# 10_SENSORS_CAN_485.net
KiCad netlist of a schematic drawn in Altium Designer
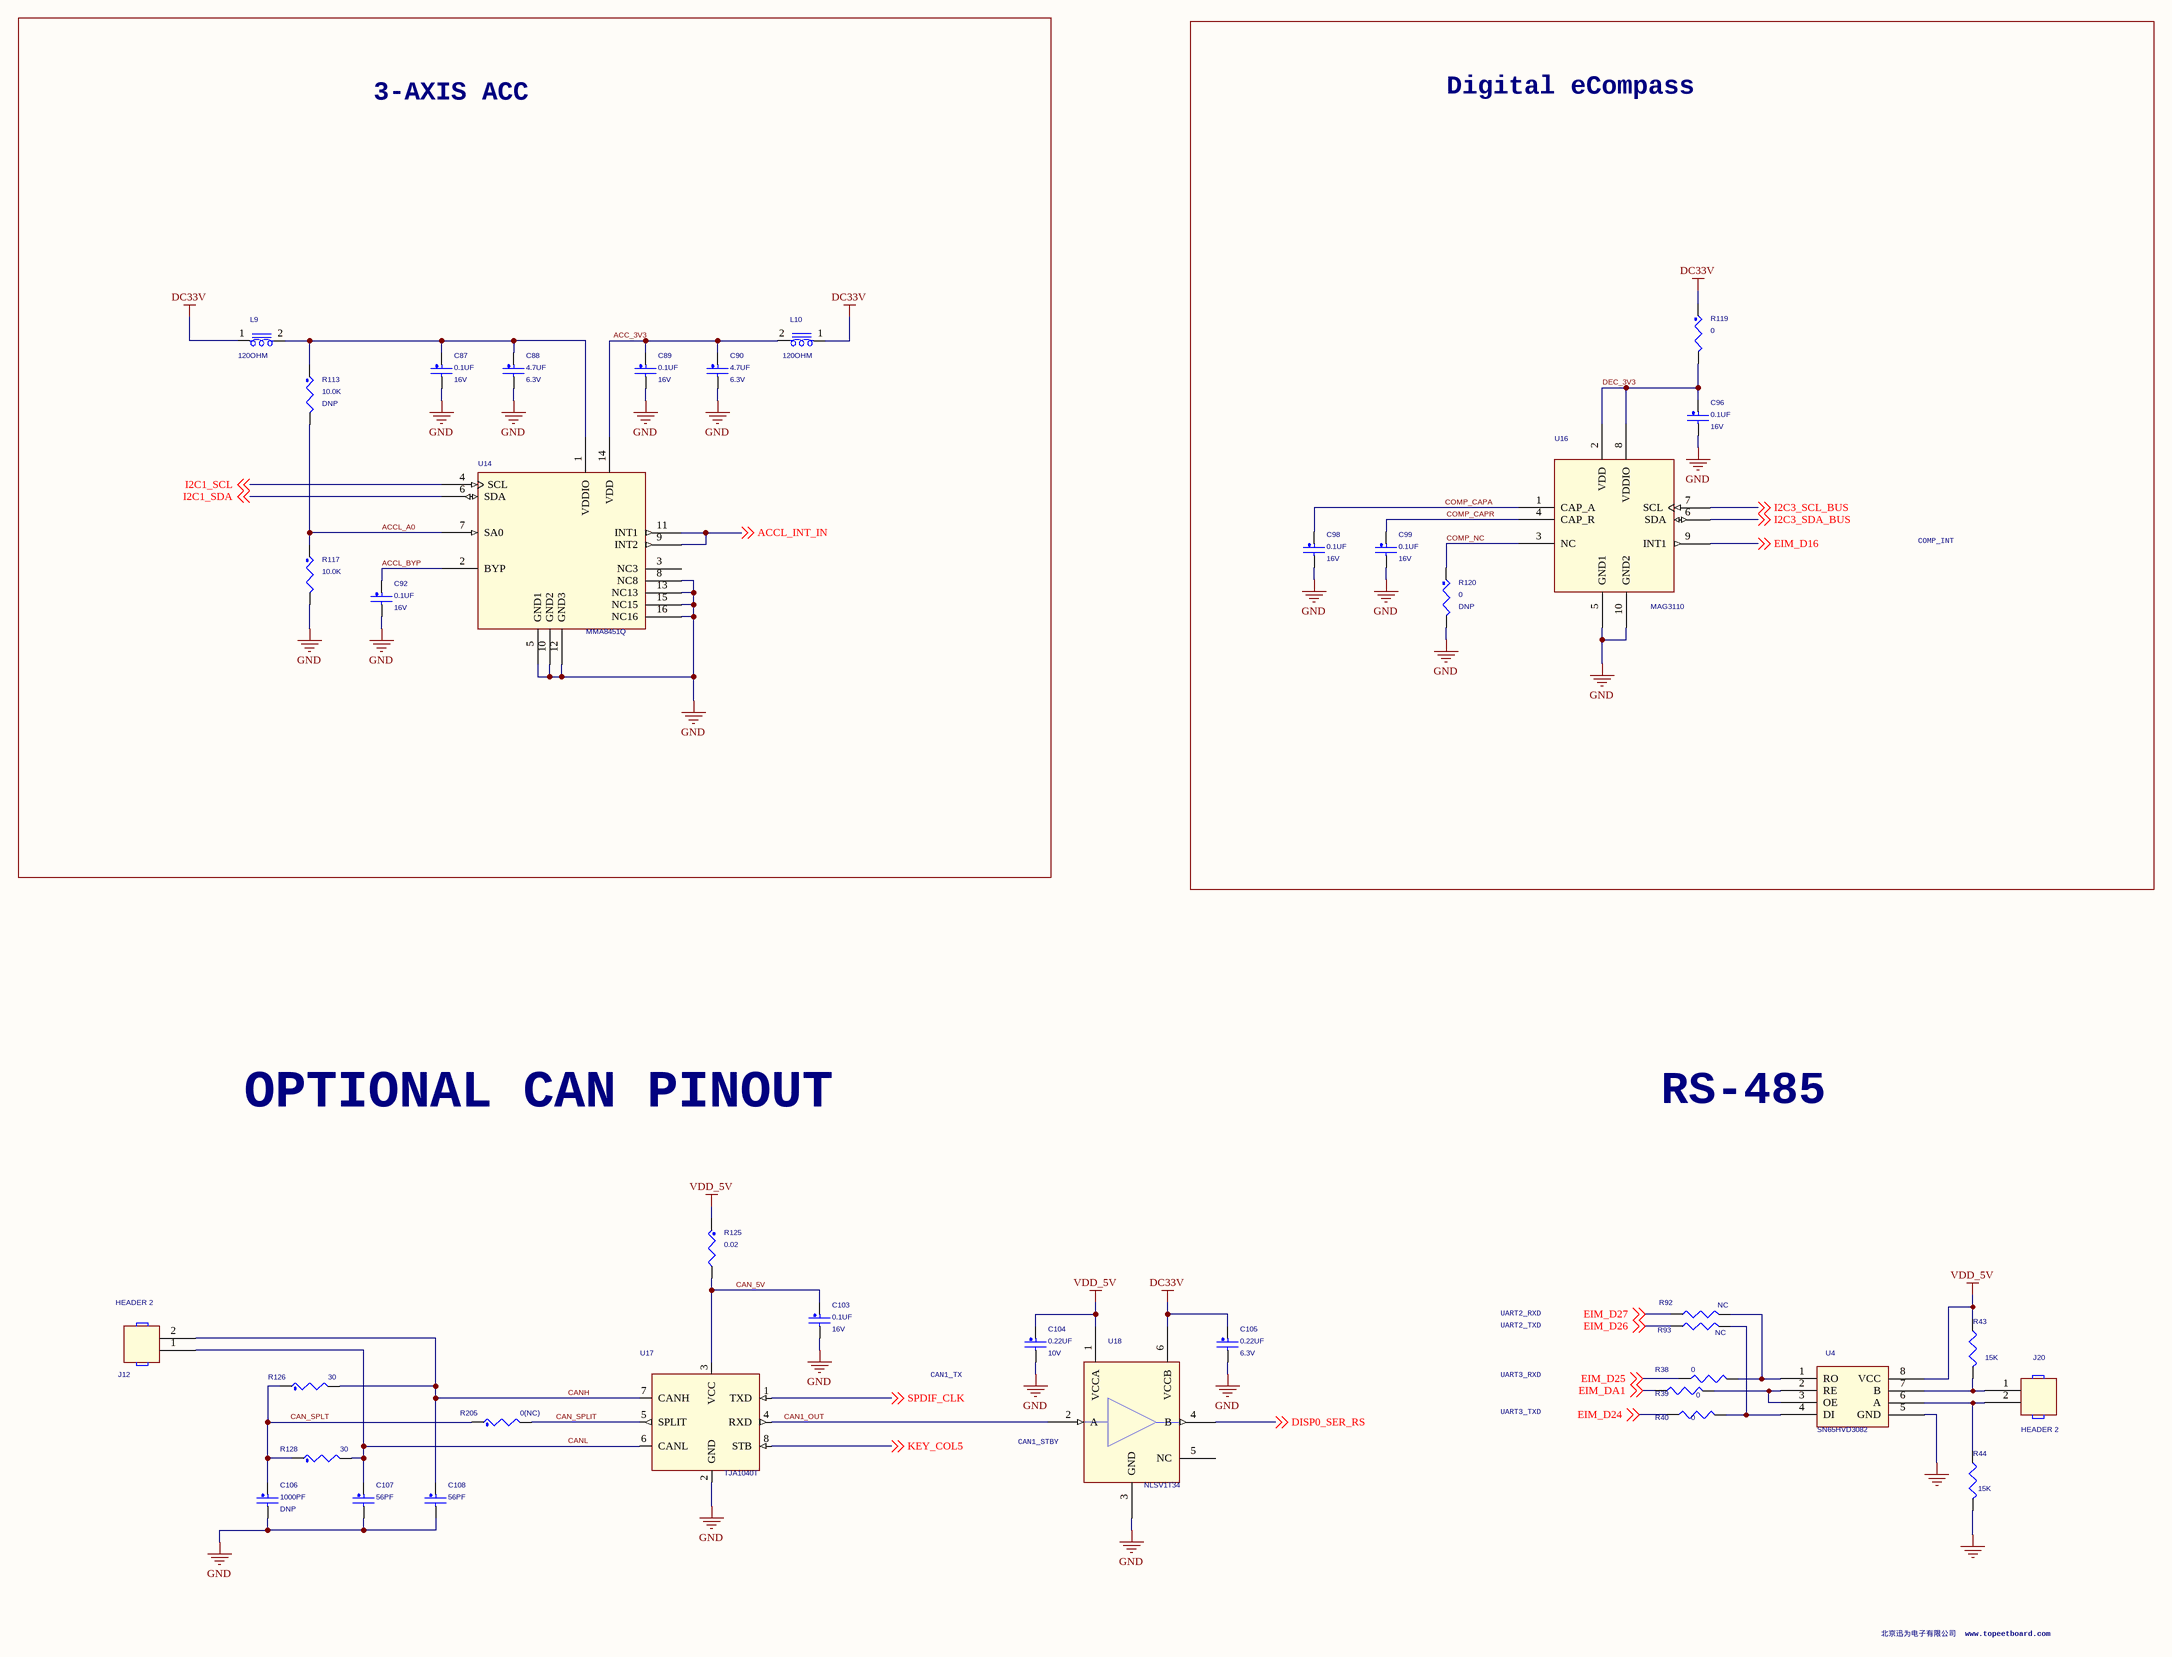
[diagram p0: 10 SENSORS,CAN,485.SchDoc]

(export (version "E")
  (design (tool "Eeschema 10.0.6"))
  (components
    (comp (ref "C87")
      (value "0.1UF")
      (description "CAP CER 0.1UF 16V 10% X7R 0402")
      (fields (field (name "TOLERANCE") "10%") (field (name "WVDC") "16V") (field (name "VOLTAGE") "16V"))
      (libsource (lib "*") (part "CAP_NP"))
    )
    (comp (ref "C88")
      (value "4.7UF")
      (description "CAP CER 4.7UF 6.3V 10% X5R 0603")
      (fields (field (name "TOLERANCE") "10%") (field (name "WVDC") "6.3V") (field (name "VOLTAGE") "6.3V"))
      (libsource (lib "*") (part "CAP_NP"))
    )
    (comp (ref "C89")
      (value "0.1UF")
      (description "CAP CER 0.1UF 16V 10% X7R 0402")
      (fields (field (name "TOLERANCE") "10%") (field (name "WVDC") "16V") (field (name "VOLTAGE") "16V"))
      (libsource (lib "*") (part "CAP_NP"))
    )
    (comp (ref "C90")
      (value "4.7UF")
      (description "CAP CER 4.7UF 6.3V 10% X5R 0603")
      (fields (field (name "VOLTAGE") "6.3V") (field (name "WVDC") "6.3V") (field (name "TOLERANCE") "10%"))
      (libsource (lib "*") (part "CAP_NP"))
    )
    (comp (ref "C92")
      (value "0.1UF")
      (description "CAP CER 0.1UF 16V 10% X7R 0402")
      (fields (field (name "VOLTAGE") "16V") (field (name "WVDC") "16V") (field (name "TOLERANCE") "10%"))
      (libsource (lib "*") (part "CAP_NP"))
    )
    (comp (ref "C96")
      (value "0.1UF")
      (description "CAP CER 0.1UF 16V 10% X7R 0402")
      (fields (field (name "TOLERANCE") "10%") (field (name "WVDC") "16V") (field (name "VOLTAGE") "16V"))
      (libsource (lib "*") (part "CAP_NP"))
    )
    (comp (ref "C98")
      (value "0.1UF")
      (description "CAP CER 0.1UF 16V 10% X7R 0402")
      (fields (field (name "TOLERANCE") "10%") (field (name "WVDC") "16V") (field (name "VOLTAGE") "16V"))
      (libsource (lib "*") (part "CAP_NP"))
    )
    (comp (ref "C99")
      (value "0.1UF")
      (description "CAP CER 0.1UF 16V 10% X7R 0402")
      (fields (field (name "TOLERANCE") "10%") (field (name "WVDC") "16V") (field (name "VOLTAGE") "16V"))
      (libsource (lib "*") (part "CAP_NP"))
    )
    (comp (ref "C103")
      (value "0.1UF")
      (description "CAP CER 0.1UF 16V 10% X7R 0402")
      (fields (field (name "VOLTAGE") "16V") (field (name "TOLERANCE") "10%") (field (name "WVDC") "16V"))
      (libsource (lib "*") (part "CAP_NP"))
    )
    (comp (ref "C104")
      (value "0.22UF")
      (description "CAP CER 0.22UF 10V 20% X5R 0201")
      (fields (field (name "VOLTAGE") "10V") (field (name "TOLERANCE") "20%") (field (name "WVDC") "10V"))
      (libsource (lib "*") (part "CAP_NP"))
    )
    (comp (ref "C105")
      (value "0.22UF")
      (description "CAP CER 0.22UF 6.3V 20% X5R 0201")
      (fields (field (name "VOLTAGE") "6.3V") (field (name "WVDC") "6.3V") (field (name "TOLERANCE") "20%"))
      (libsource (lib "*") (part "CAP_NP"))
    )
    (comp (ref "C106")
      (value "1000PF")
      (description "CAP CER 1000PF 50V 5% C0G 0402")
      (fields (field (name "ASSY_OPT") "DNP"))
      (libsource (lib "*") (part "CAP_NP"))
    )
    (comp (ref "C107")
      (value "56PF")
      (description "CAP CER 56PF 25V 5% C0G CC0201")
      (fields (field (name "VOLTAGE") "25V") (field (name "TOLERANCE") "5%"))
      (libsource (lib "*") (part "CAP_NP"))
    )
    (comp (ref "C108")
      (value "56PF")
      (description "CAP CER 56PF 25V 5% C0G CC0201")
      (fields (field (name "VOLTAGE") "25V") (field (name "TOLERANCE") "5%"))
      (libsource (lib "*") (part "CAP_NP"))
    )
    (comp (ref "J12") (value "HEADER 2") (libsource (lib "*") (part "HEADER 2")))
    (comp (ref "J20") (value "HEADER 2") (libsource (lib "") (part "HEADER 2_1")))
    (comp (ref "L9")
      (value "120OHM")
      (description "IND FER BEAD 120OHM@100MHZ 2A 25% 0603")
      (fields (field (name "TOLERANCE") "25%"))
      (libsource (lib "") (part "BEAD_0_1"))
    )
    (comp (ref "L10")
      (value "120OHM")
      (description "IND FER BEAD 120OHM@100MHZ 2A 25% 0603")
      (fields (field (name "TOLERANCE") "25%"))
      (libsource (lib "*") (part "BEAD_0"))
    )
    (comp (ref "R38") (value "0") (footprint "R1005") (libsource (lib "*") (part "R1005_0_Dup1")))
    (comp (ref "R39") (value "0") (footprint "R1005") (libsource (lib "*") (part "R1005_0_Dup1")))
    (comp (ref "R40") (value "0") (footprint "R1005") (libsource (lib "*") (part "R1005_0_Dup1")))
    (comp (ref "R43") (value "15K") (footprint "R1005") (libsource (lib "*") (part "R1005_0_Dup1")))
    (comp (ref "R44") (value "15K") (footprint "R1005") (libsource (lib "*") (part "R1005_0_Dup1")))
    (comp (ref "R92") (value "NC") (footprint "R1005") (libsource (lib "*") (part "R1005_0_Dup1")))
    (comp (ref "R93") (value "NC") (footprint "R1005") (libsource (lib "*") (part "R1005_0_Dup1")))
    (comp (ref "R113")
      (value "10.0K")
      (description "RES MF 10.0K 1/16W 1% AEC-Q200 0402")
      (fields (field (name "ASSY_OPT") "DNP") (field (name "TOLERANCE") "1%"))
      (libsource (lib "*") (part "RES_Dup1"))
    )
    (comp (ref "R117")
      (value "10.0K")
      (description "RES MF 10.0K 1/16W 1% AEC-Q200 0402")
      (fields (field (name "TOLERANCE") "1%"))
      (libsource (lib "*") (part "RES_Dup1"))
    )
    (comp (ref "R119")
      (value "0")
      (description "RES MF ZERO OHM 1/10W -- 0402")
      (libsource (lib "*") (part "RES_Dup1"))
    )
    (comp (ref "R120")
      (value "0")
      (description "RES MF ZERO OHM 1/10W -- 0402")
      (fields (field (name "ASSY_OPT") "DNP"))
      (libsource (lib "*") (part "RES_Dup1"))
    )
    (comp (ref "R125")
      (value "0.02")
      (description "RES MF 0.02 OHM 1/8W 1% 0805")
      (libsource (lib "*") (part "RES_Dup1"))
    )
    (comp (ref "R126")
      (value "30")
      (description "RES MF 30 OHM 1/16W 1% 0402")
      (fields (field (name "TOLERANCE") "1%"))
      (libsource (lib "*") (part "RES_Dup1"))
    )
    (comp (ref "R128")
      (value "30")
      (description "RES MF 30 OHM 1/16W 1% 0402")
      (fields (field (name "TOLERANCE") "1%"))
      (libsource (lib "*") (part "RES_Dup1"))
    )
    (comp (ref "R205")
      (value "0(NC)")
      (description "RES MF 30 OHM 1/16W 1% 0402")
      (fields (field (name "TOLERANCE") "1%"))
      (libsource (lib "*") (part "RES_Dup1"))
    )
    (comp (ref "U4") (value "SN65HVD3082") (libsource (lib "*") (part "SN65HVD3082")))
    (comp (ref "U14")
      (value "MMA8451Q")
      (description "IC 3-AXIS DIG ACCELEROMETER 14/8BIT 1.95-3.6V QFN16")
      (libsource (lib "*") (part "MMA8451Q_16P_A"))
    )
    (comp (ref "U16")
      (value "MAG3110")
      (description "IC 3-AXIS DIGITAL MAGNETOMETER 1.95-3.6V DFN10")
      (libsource (lib "*") (part "MAG3112_DFN_10P"))
    )
    (comp (ref "U17")
      (value "TJA1040T")
      (description "IC XCVR CAN HS 5V SO8")
      (libsource (lib "*") (part "TJA1040T_SO_8P"))
    )
    (comp (ref "U18")
      (value "NLSV1T34")
      (description "IC VXLTR 1 BIT DUAL-SUPPLY 0.9-4.5V 613AF")
      (libsource (lib "*") (part "NLSV1T34"))
    )
  )
  (nets
    (net (code "1") (name "/ACCL_A0") (class "Default")
      (node (ref "R113") (pin "2") (pinfunction "2_2") (pintype "passive"))
      (node (ref "R117") (pin "1") (pinfunction "1_1") (pintype "passive"))
      (node (ref "U14") (pin "7") (pinfunction "SA0_7") (pintype "input"))
    )
    (net (code "2") (name "/ACCL_BYP") (class "Default")
      (node (ref "C92") (pin "1") (pinfunction "1_1") (pintype "passive"))
      (node (ref "U14") (pin "2") (pinfunction "BYP_2") (pintype "passive"))
    )
    (net (code "3") (name "/ACC_3V3") (class "Default")
      (node (ref "C89") (pin "1") (pinfunction "1_1") (pintype "passive"))
      (node (ref "C90") (pin "1") (pinfunction "1_1") (pintype "passive"))
      (node (ref "L10") (pin "2") (pinfunction "2_2") (pintype "passive"))
      (node (ref "U14") (pin "14") (pinfunction "VDD_14") (pintype "power_in"))
    )
    (net (code "4") (name "/CAN1_OUT") (class "Default")
      (node (ref "U17") (pin "4") (pinfunction "RXD_4") (pintype "output"))
      (node (ref "U18") (pin "2") (pinfunction "A_2") (pintype "input"))
    )
    (net (code "5") (name "/CANH") (class "Default")
      (node (ref "C108") (pin "1") (pinfunction "1_1") (pintype "passive"))
      (node (ref "J12") (pin "2") (pinfunction "2_2") (pintype "passive"))
      (node (ref "R126") (pin "2") (pinfunction "2_2") (pintype "passive"))
      (node (ref "U17") (pin "7") (pinfunction "CANH_7") (pintype "bidirectional"))
    )
    (net (code "6") (name "/CANL") (class "Default")
      (node (ref "C107") (pin "1") (pinfunction "1_1") (pintype "passive"))
      (node (ref "J12") (pin "1") (pinfunction "1_1") (pintype "passive"))
      (node (ref "R128") (pin "2") (pinfunction "2_2") (pintype "passive"))
      (node (ref "U17") (pin "6") (pinfunction "CANL_6") (pintype "bidirectional"))
    )
    (net (code "7") (name "/CAN_5V") (class "Default")
      (node (ref "C103") (pin "1") (pinfunction "1_1") (pintype "passive"))
      (node (ref "R125") (pin "2") (pinfunction "2_2") (pintype "passive"))
      (node (ref "U17") (pin "3") (pinfunction "VCC_3") (pintype "power_in"))
    )
    (net (code "8") (name "/CAN_SPLIT") (class "Default")
      (node (ref "R205") (pin "2") (pinfunction "2_2") (pintype "passive"))
      (node (ref "U17") (pin "5") (pinfunction "SPLIT_5") (pintype "output"))
    )
    (net (code "9") (name "/CAN_SPLT") (class "Default")
      (node (ref "C106") (pin "1") (pinfunction "1_1") (pintype "passive"))
      (node (ref "R126") (pin "1") (pinfunction "1_1") (pintype "passive"))
      (node (ref "R128") (pin "1") (pinfunction "1_1") (pintype "passive"))
      (node (ref "R205") (pin "1") (pinfunction "1_1") (pintype "passive"))
    )
    (net (code "10") (name "/COMP_CAPA") (class "Default")
      (node (ref "C98") (pin "1") (pinfunction "1_1") (pintype "passive"))
      (node (ref "U16") (pin "1") (pinfunction "CAP_A_1") (pintype "passive"))
    )
    (net (code "11") (name "/COMP_CAPR") (class "Default")
      (node (ref "C99") (pin "1") (pinfunction "1_1") (pintype "passive"))
      (node (ref "U16") (pin "4") (pinfunction "CAP_R_4") (pintype "passive"))
    )
    (net (code "12") (name "/COMP_NC") (class "Default")
      (node (ref "R120") (pin "1") (pinfunction "1_1") (pintype "passive"))
      (node (ref "U16") (pin "3") (pinfunction "NC_3") (pintype "passive"))
    )
    (net (code "13") (name "/DEC_3V3") (class "Default")
      (node (ref "C96") (pin "1") (pinfunction "1_1") (pintype "passive"))
      (node (ref "R119") (pin "2") (pinfunction "2_2") (pintype "passive"))
      (node (ref "U16") (pin "2") (pinfunction "VDD_2") (pintype "power_in"))
      (node (ref "U16") (pin "8") (pinfunction "VDDIO_8") (pintype "power_in"))
    )
    (net (code "14") (name "ACCL_INT_IN") (class "Default")
      (node (ref "U14") (pin "11") (pinfunction "INT1_11") (pintype "output"))
      (node (ref "U14") (pin "9") (pinfunction "INT2_9") (pintype "output"))
    )
    (net (code "15") (name "DC33V") (class "Default")
      (node (ref "C105") (pin "1") (pinfunction "1_1") (pintype "passive"))
      (node (ref "L10") (pin "1") (pinfunction "1_1") (pintype "passive"))
      (node (ref "L9") (pin "1") (pinfunction "1_1") (pintype "passive"))
      (node (ref "R119") (pin "1") (pinfunction "1_1") (pintype "passive"))
      (node (ref "U18") (pin "6") (pinfunction "VCCB_6") (pintype "power_in"))
    )
    (net (code "16") (name "DISP0_SER_RS") (class "Default")
      (node (ref "U18") (pin "4") (pinfunction "B_4") (pintype "output"))
    )
    (net (code "17") (name "EIM_D16") (class "Default")
      (node (ref "U16") (pin "9") (pinfunction "INT1_9") (pintype "output"))
    )
    (net (code "18") (name "EIM_D24") (class "Default")
      (node (ref "R40") (pin "2") (pinfunction "2_2") (pintype "passive"))
    )
    (net (code "19") (name "EIM_D25") (class "Default")
      (node (ref "R38") (pin "2") (pinfunction "2_2") (pintype "passive"))
    )
    (net (code "20") (name "EIM_D26") (class "Default")
      (node (ref "R93") (pin "1") (pinfunction "1_1") (pintype "passive"))
    )
    (net (code "21") (name "EIM_D27") (class "Default")
      (node (ref "R92") (pin "1") (pinfunction "1_1") (pintype "passive"))
    )
    (net (code "22") (name "EIM_DA1") (class "Default")
      (node (ref "R39") (pin "2") (pinfunction "2_2") (pintype "passive"))
    )
    (net (code "23") (name "GND") (class "Default")
      (node (ref "C103") (pin "2") (pinfunction "2_2") (pintype "passive"))
      (node (ref "C104") (pin "2") (pinfunction "2_2") (pintype "passive"))
      (node (ref "C105") (pin "2") (pinfunction "2_2") (pintype "passive"))
      (node (ref "C106") (pin "2") (pinfunction "2_2") (pintype "passive"))
      (node (ref "C107") (pin "2") (pinfunction "2_2") (pintype "passive"))
      (node (ref "C108") (pin "2") (pinfunction "2_2") (pintype "passive"))
      (node (ref "C87") (pin "2") (pinfunction "2_2") (pintype "passive"))
      (node (ref "C88") (pin "2") (pinfunction "2_2") (pintype "passive"))
      (node (ref "C89") (pin "2") (pinfunction "2_2") (pintype "passive"))
      (node (ref "C90") (pin "2") (pinfunction "2_2") (pintype "passive"))
      (node (ref "C92") (pin "2") (pinfunction "2_2") (pintype "passive"))
      (node (ref "C96") (pin "2") (pinfunction "2_2") (pintype "passive"))
      (node (ref "C98") (pin "2") (pinfunction "2_2") (pintype "passive"))
      (node (ref "C99") (pin "2") (pinfunction "2_2") (pintype "passive"))
      (node (ref "R117") (pin "2") (pinfunction "2_2") (pintype "passive"))
      (node (ref "R120") (pin "2") (pinfunction "2_2") (pintype "passive"))
      (node (ref "R44") (pin "1") (pinfunction "1_1") (pintype "passive"))
      (node (ref "U14") (pin "10") (pinfunction "GND2_10") (pintype "power_in"))
      (node (ref "U14") (pin "12") (pinfunction "GND3_12") (pintype "power_in"))
      (node (ref "U14") (pin "13") (pinfunction "NC13_13") (pintype "passive"))
      (node (ref "U14") (pin "15") (pinfunction "NC15_15") (pintype "passive"))
      (node (ref "U14") (pin "16") (pinfunction "NC16_16") (pintype "passive"))
      (node (ref "U14") (pin "5") (pinfunction "GND1_5") (pintype "power_in"))
      (node (ref "U14") (pin "8") (pinfunction "NC8_8") (pintype "passive"))
      (node (ref "U16") (pin "10") (pinfunction "GND2_10") (pintype "power_in"))
      (node (ref "U16") (pin "5") (pinfunction "GND1_5") (pintype "power_in"))
      (node (ref "U17") (pin "2") (pinfunction "GND_2") (pintype "power_in"))
      (node (ref "U18") (pin "3") (pinfunction "GND_3") (pintype "power_in"))
      (node (ref "U4") (pin "5") (pinfunction "GND_5") (pintype "passive"))
    )
    (net (code "24") (name "I2C1_SCL") (class "Default")
      (node (ref "U14") (pin "4") (pinfunction "SCL_4") (pintype "input"))
    )
    (net (code "25") (name "I2C1_SDA") (class "Default")
      (node (ref "U14") (pin "6") (pinfunction "SDA_6") (pintype "bidirectional"))
    )
    (net (code "26") (name "I2C3_SCL_BUS") (class "Default")
      (node (ref "U16") (pin "7") (pinfunction "SCL_7") (pintype "input"))
    )
    (net (code "27") (name "I2C3_SDA_BUS") (class "Default")
      (node (ref "U16") (pin "6") (pinfunction "SDA_6") (pintype "bidirectional"))
    )
    (net (code "28") (name "KEY_COL5") (class "Default")
      (node (ref "U17") (pin "8") (pinfunction "STB_8") (pintype "input"))
    )
    (net (code "29") (name "Net-(U4-A)") (class "Default")
      (node (ref "J20") (pin "2") (pinfunction "2_2") (pintype "passive"))
      (node (ref "R44") (pin "2") (pinfunction "2_2") (pintype "passive"))
      (node (ref "U4") (pin "6") (pinfunction "A_6") (pintype "passive"))
    )
    (net (code "30") (name "Net-(U4-B)") (class "Default")
      (node (ref "J20") (pin "1") (pinfunction "1_1") (pintype "passive"))
      (node (ref "R43") (pin "1") (pinfunction "1_1") (pintype "passive"))
      (node (ref "U4") (pin "7") (pinfunction "B_7") (pintype "passive"))
    )
    (net (code "31") (name "Net-(U4-DI)") (class "Default")
      (node (ref "R40") (pin "1") (pinfunction "1_1") (pintype "passive"))
      (node (ref "R93") (pin "2") (pinfunction "2_2") (pintype "passive"))
      (node (ref "U4") (pin "4") (pinfunction "DI_4") (pintype "passive"))
    )
    (net (code "32") (name "Net-(U4-OE)") (class "Default")
      (node (ref "R39") (pin "1") (pinfunction "1_1") (pintype "passive"))
      (node (ref "U4") (pin "2") (pinfunction "RE_2") (pintype "passive"))
      (node (ref "U4") (pin "3") (pinfunction "OE_3") (pintype "passive"))
    )
    (net (code "33") (name "Net-(U4-RO)") (class "Default")
      (node (ref "R38") (pin "1") (pinfunction "1_1") (pintype "passive"))
      (node (ref "R92") (pin "2") (pinfunction "2_2") (pintype "passive"))
      (node (ref "U4") (pin "1") (pinfunction "RO_1") (pintype "passive"))
    )
    (net (code "34") (name "Net-(U14-VDDIO)") (class "Default")
      (node (ref "C87") (pin "1") (pinfunction "1_1") (pintype "passive"))
      (node (ref "C88") (pin "1") (pinfunction "1_1") (pintype "passive"))
      (node (ref "L9") (pin "2") (pinfunction "2_2") (pintype "passive"))
      (node (ref "R113") (pin "1") (pinfunction "1_1") (pintype "passive"))
      (node (ref "U14") (pin "1") (pinfunction "VDDIO_1") (pintype "power_in"))
    )
    (net (code "35") (name "SPDIF_CLK") (class "Default")
      (node (ref "U17") (pin "1") (pinfunction "TXD_1") (pintype "input"))
    )
    (net (code "36") (name "VDD_5V") (class "Default")
      (node (ref "C104") (pin "1") (pinfunction "1_1") (pintype "passive"))
      (node (ref "R125") (pin "1") (pinfunction "1_1") (pintype "passive"))
      (node (ref "R43") (pin "2") (pinfunction "2_2") (pintype "passive"))
      (node (ref "U18") (pin "1") (pinfunction "VCCA_1") (pintype "power_in"))
      (node (ref "U4") (pin "8") (pinfunction "VCC_8") (pintype "passive"))
    )
    (net (code "37") (name "unconnected-(U14-NC3-Pad3)") (class "Default")
      (node (ref "U14") (pin "3") (pinfunction "NC3_3") (pintype "passive"))
    )
    (net (code "38") (name "unconnected-(U18-NC-Pad5)") (class "Default")
      (node (ref "U18") (pin "5") (pinfunction "NC_5") (pintype "passive"))
    )
  )
)
